# MCU.net
KiCad netlist of a schematic drawn in Altium Designer
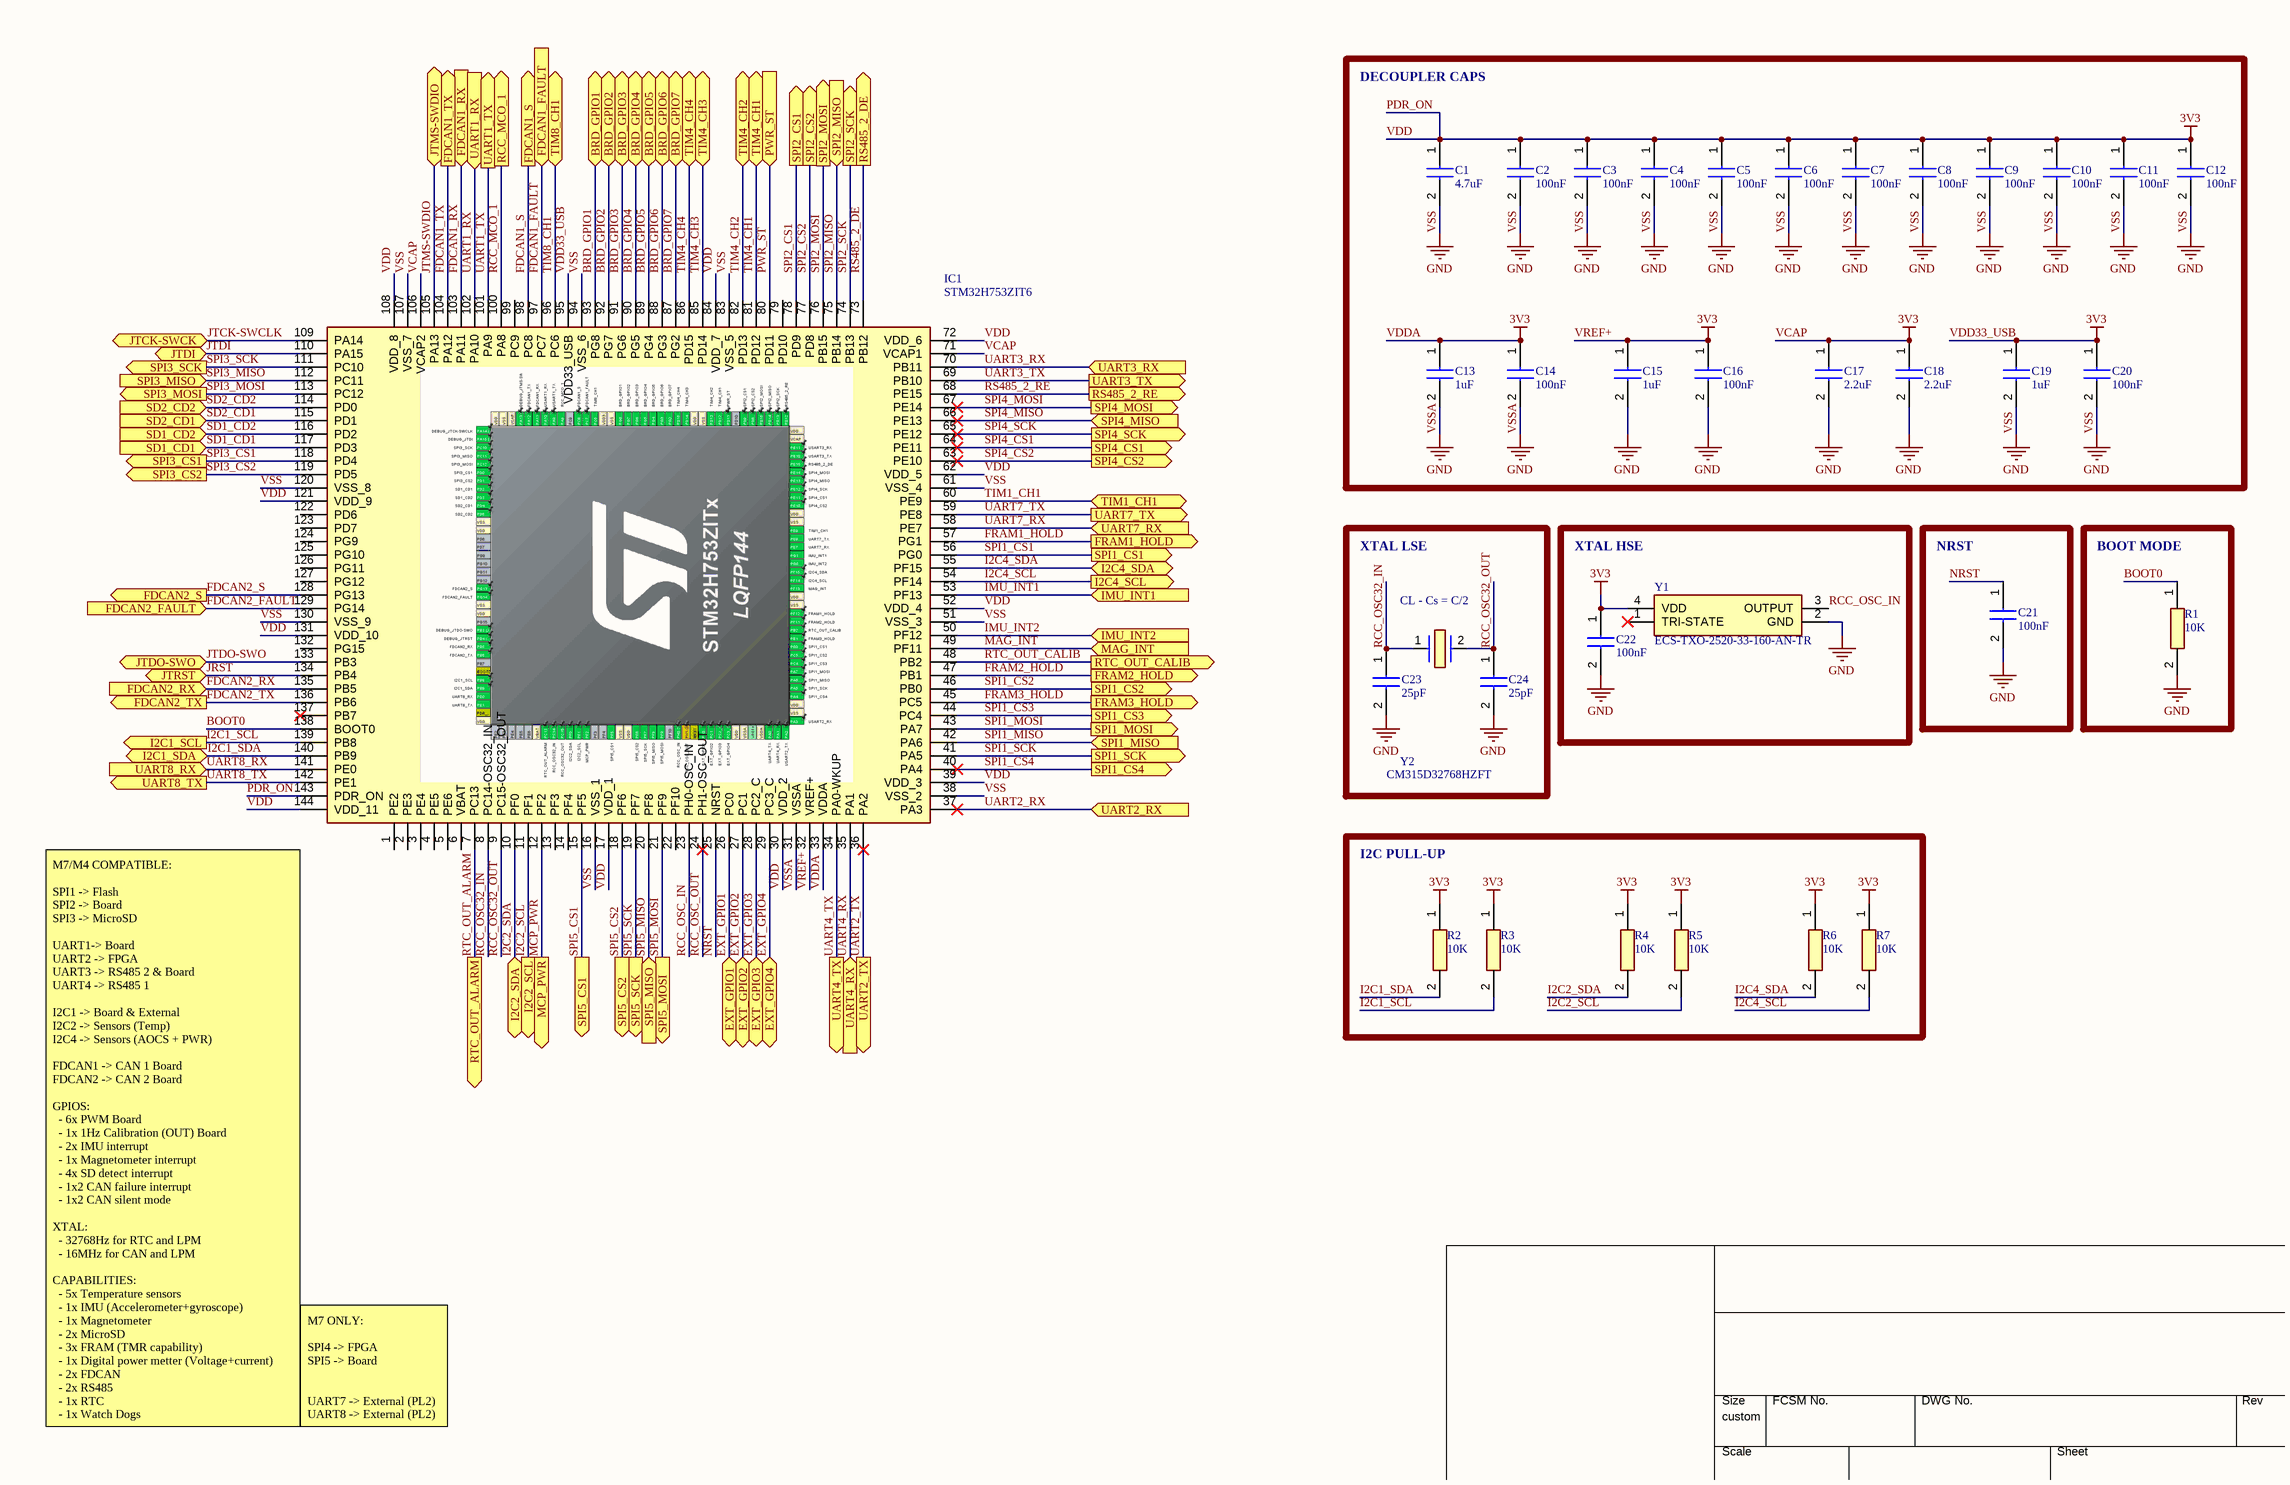
[diagram p0: MCU.SchDoc]

(export (version "E")
  (design (tool "Eeschema 10.0.6"))
  (components
    (comp (ref "C1")
      (value "4.7uF")
      (footprint "RT_IS:CAPC1608X90N")
      (description "4.7 µF ±10% 10V Ceramic Capacitor X5R 0603 (1608 Metric)")
      (fields
        (field (name "MANUFACTURER_PART_NUMBER") "CL10A475KP8NNNC")
        (field (name "MOUSER PART NUMBER") "187-CL10A475KP8NNNC")
      )
      (libsource (lib "*") (part "CL10A475KP8NNNC"))
    )
    (comp (ref "C2")
      (value "100nF")
      (footprint "RT_IS:CAPC1608X95N")
      (description "0.1 µF ±20% 16V Ceramic Capacitor X7R 0603 (1608 Metric)")
      (fields (field (name "MANUFACTURER_PART_NUMBER") "C0603C104M4RAC7867"))
      (libsource (lib "*") (part "C0603C104M4RAC7867"))
    )
    (comp (ref "C3")
      (value "100nF")
      (footprint "RT_IS:CAPC1608X95N")
      (description "0.1 µF ±20% 16V Ceramic Capacitor X7R 0603 (1608 Metric)")
      (fields (field (name "MANUFACTURER_PART_NUMBER") "C0603C104M4RAC7867"))
      (libsource (lib "*") (part "C0603C104M4RAC7867"))
    )
    (comp (ref "C4")
      (value "100nF")
      (footprint "RT_IS:CAPC1608X95N")
      (description "0.1 µF ±20% 16V Ceramic Capacitor X7R 0603 (1608 Metric)")
      (fields (field (name "MANUFACTURER_PART_NUMBER") "C0603C104M4RAC7867"))
      (libsource (lib "*") (part "C0603C104M4RAC7867"))
    )
    (comp (ref "C5")
      (value "100nF")
      (footprint "RT_IS:CAPC1608X95N")
      (description "0.1 µF ±20% 16V Ceramic Capacitor X7R 0603 (1608 Metric)")
      (fields (field (name "MANUFACTURER_PART_NUMBER") "C0603C104M4RAC7867"))
      (libsource (lib "*") (part "C0603C104M4RAC7867"))
    )
    (comp (ref "C6")
      (value "100nF")
      (footprint "RT_IS:CAPC1608X95N")
      (description "0.1 µF ±20% 16V Ceramic Capacitor X7R 0603 (1608 Metric)")
      (fields (field (name "MANUFACTURER_PART_NUMBER") "C0603C104M4RAC7867"))
      (libsource (lib "*") (part "C0603C104M4RAC7867"))
    )
    (comp (ref "C7")
      (value "100nF")
      (footprint "RT_IS:CAPC1608X95N")
      (description "0.1 µF ±20% 16V Ceramic Capacitor X7R 0603 (1608 Metric)")
      (fields (field (name "MANUFACTURER_PART_NUMBER") "C0603C104M4RAC7867"))
      (libsource (lib "*") (part "C0603C104M4RAC7867"))
    )
    (comp (ref "C8")
      (value "100nF")
      (footprint "RT_IS:CAPC1608X95N")
      (description "0.1 µF ±20% 16V Ceramic Capacitor X7R 0603 (1608 Metric)")
      (fields (field (name "MANUFACTURER_PART_NUMBER") "C0603C104M4RAC7867"))
      (libsource (lib "*") (part "C0603C104M4RAC7867"))
    )
    (comp (ref "C9")
      (value "100nF")
      (footprint "RT_IS:CAPC1608X95N")
      (description "0.1 µF ±20% 16V Ceramic Capacitor X7R 0603 (1608 Metric)")
      (fields (field (name "MANUFACTURER_PART_NUMBER") "C0603C104M4RAC7867"))
      (libsource (lib "*") (part "C0603C104M4RAC7867"))
    )
    (comp (ref "C10")
      (value "100nF")
      (footprint "RT_IS:CAPC1608X95N")
      (description "0.1 µF ±20% 16V Ceramic Capacitor X7R 0603 (1608 Metric)")
      (fields (field (name "MANUFACTURER_PART_NUMBER") "C0603C104M4RAC7867"))
      (libsource (lib "*") (part "C0603C104M4RAC7867"))
    )
    (comp (ref "C11")
      (value "100nF")
      (footprint "RT_IS:CAPC1608X95N")
      (description "0.1 µF ±20% 16V Ceramic Capacitor X7R 0603 (1608 Metric)")
      (fields (field (name "MANUFACTURER_PART_NUMBER") "C0603C104M4RAC7867"))
      (libsource (lib "*") (part "C0603C104M4RAC7867"))
    )
    (comp (ref "C12")
      (value "100nF")
      (footprint "RT_IS:CAPC1608X95N")
      (description "0.1 µF ±20% 16V Ceramic Capacitor X7R 0603 (1608 Metric)")
      (fields (field (name "MANUFACTURER_PART_NUMBER") "C0603C104M4RAC7867"))
      (libsource (lib "*") (part "C0603C104M4RAC7867"))
    )
    (comp (ref "C13")
      (value "1uF")
      (footprint "RT_IS:CAPC1608X90N")
      (description "1 µF ±10% 25V Ceramic Capacitor X5R 0603 (1608 Metric)")
      (fields
        (field (name "MANUFACTURER_PART_NUMBER") "CL10A105KA8NNNC")
        (field (name "MOUSER PART NUMBER") "187-CL10A105KA8NNNC")
      )
      (libsource (lib "*") (part "CL10A105KA8NNNC"))
    )
    (comp (ref "C14")
      (value "100nF")
      (footprint "RT_IS:CAPC1608X95N")
      (description "0.1 µF ±20% 16V Ceramic Capacitor X7R 0603 (1608 Metric)")
      (fields (field (name "MANUFACTURER_PART_NUMBER") "C0603C104M4RAC7867"))
      (libsource (lib "*") (part "C0603C104M4RAC7867"))
    )
    (comp (ref "C15")
      (value "1uF")
      (footprint "RT_IS:CAPC1608X90N")
      (description "1 µF ±10% 25V Ceramic Capacitor X5R 0603 (1608 Metric)")
      (fields
        (field (name "MANUFACTURER_PART_NUMBER") "CL10A105KA8NNNC")
        (field (name "MOUSER PART NUMBER") "187-CL10A105KA8NNNC")
      )
      (libsource (lib "*") (part "CL10A105KA8NNNC"))
    )
    (comp (ref "C16")
      (value "100nF")
      (footprint "RT_IS:CAPC1608X95N")
      (description "0.1 µF ±20% 16V Ceramic Capacitor X7R 0603 (1608 Metric)")
      (fields (field (name "MANUFACTURER_PART_NUMBER") "C0603C104M4RAC7867"))
      (libsource (lib "*") (part "C0603C104M4RAC7867"))
    )
    (comp (ref "C17")
      (value "2.2uF")
      (footprint "RT_IS:CAPC1608X90N")
      (description "2.2 µF ±10% 16V Ceramic Capacitor X5R 0603 (1608 Metric)")
      (fields
        (field (name "MANUFACTURER_PART_NUMBER") "CL10A225KO8NNNC")
        (field (name "MOUSER PART NUMBER") "187-CL10A225KO8NNNC")
      )
      (libsource (lib "*") (part "CL10A225KO8NNNC"))
    )
    (comp (ref "C18")
      (value "2.2uF")
      (footprint "RT_IS:CAPC1608X90N")
      (description "2.2 µF ±10% 16V Ceramic Capacitor X5R 0603 (1608 Metric)")
      (fields
        (field (name "MANUFACTURER_PART_NUMBER") "CL10A225KO8NNNC")
        (field (name "MOUSER PART NUMBER") "187-CL10A225KO8NNNC")
      )
      (libsource (lib "*") (part "CL10A225KO8NNNC"))
    )
    (comp (ref "C19")
      (value "1uF")
      (footprint "RT_IS:CAPC1608X90N")
      (description "1 µF ±10% 25V Ceramic Capacitor X5R 0603 (1608 Metric)")
      (fields
        (field (name "MANUFACTURER_PART_NUMBER") "CL10A105KA8NNNC")
        (field (name "MOUSER PART NUMBER") "187-CL10A105KA8NNNC")
      )
      (libsource (lib "*") (part "CL10A105KA8NNNC"))
    )
    (comp (ref "C20")
      (value "100nF")
      (footprint "RT_IS:CAPC1608X95N")
      (description "0.1 µF ±20% 16V Ceramic Capacitor X7R 0603 (1608 Metric)")
      (fields (field (name "MANUFACTURER_PART_NUMBER") "C0603C104M4RAC7867"))
      (libsource (lib "*") (part "C0603C104M4RAC7867"))
    )
    (comp (ref "C21")
      (value "100nF")
      (footprint "RT_IS:CAPC1608X95N")
      (description "0.1 µF ±20% 16V Ceramic Capacitor X7R 0603 (1608 Metric)")
      (fields (field (name "MANUFACTURER_PART_NUMBER") "C0603C104M4RAC7867"))
      (libsource (lib "*") (part "C0603C104M4RAC7867"))
    )
    (comp (ref "C22")
      (value "100nF")
      (footprint "RT_IS:CAPC1608X95N")
      (description "0.1 µF ±20% 16V Ceramic Capacitor X7R 0603 (1608 Metric)")
      (fields (field (name "MANUFACTURER_PART_NUMBER") "C0603C104M4RAC7867"))
      (libsource (lib "*") (part "C0603C104M4RAC7867"))
    )
    (comp (ref "C23")
      (value "25pF")
      (footprint "RT_IS:CAPC1608X90N")
      (description "22 pF ±1% 100V Ceramic Capacitor C0G, NP0 0603 (1608 Metric)")
      (fields (field (name "MANUFACTURER_PART_NUMBER") "GCM1885C2A220FA16D"))
      (libsource (lib "*") (part "GCM1885C2A220FA16D"))
    )
    (comp (ref "C24")
      (value "25pF")
      (footprint "RT_IS:CAPC1608X90N")
      (description "22 pF ±1% 100V Ceramic Capacitor C0G, NP0 0603 (1608 Metric)")
      (fields (field (name "MANUFACTURER_PART_NUMBER") "GCM1885C2A220FA16D"))
      (libsource (lib "*") (part "GCM1885C2A220FA16D"))
    )
    (comp (ref "IC1")
      (value "STM32H753ZIT6")
      (footprint "RT_IS:QFP50P2200X2200X160-144N")
      (fields (field (name "MOUSER PART NUMBER") "511-STM32H753ZIT6"))
      (libsource (lib "*") (part "STM32H753ZIT6"))
    )
    (comp (ref "R1")
      (value "10K")
      (footprint "RT_IS:RESC1508X50N")
      (description "10 kOhms ±1% 0.125W, 1/8W Chip Resistor 0603 (1608 Metric) Anti-Sulfur Thin Film")
      (fields
        (field (name "MANUFACTURER_PART_NUMBER") "RNCP0603FTD10K0")
        (field (name "MOUSER PART NUMBER") "708-RNCP0603FTD10K0")
      )
      (libsource (lib "*") (part "RNCP0603FTD10K0"))
    )
    (comp (ref "R2")
      (value "10K")
      (footprint "RT_IS:RESC1508X50N")
      (description "10 kOhms ±1% 0.125W, 1/8W Chip Resistor 0603 (1608 Metric) Anti-Sulfur Thin Film")
      (fields
        (field (name "MANUFACTURER_PART_NUMBER") "RNCP0603FTD10K0")
        (field (name "MOUSER PART NUMBER") "708-RNCP0603FTD10K0")
      )
      (libsource (lib "*") (part "RNCP0603FTD10K0"))
    )
    (comp (ref "R3")
      (value "10K")
      (footprint "RT_IS:RESC1508X50N")
      (description "10 kOhms ±1% 0.125W, 1/8W Chip Resistor 0603 (1608 Metric) Anti-Sulfur Thin Film")
      (fields
        (field (name "MANUFACTURER_PART_NUMBER") "RNCP0603FTD10K0")
        (field (name "MOUSER PART NUMBER") "708-RNCP0603FTD10K0")
      )
      (libsource (lib "*") (part "RNCP0603FTD10K0"))
    )
    (comp (ref "R4")
      (value "10K")
      (footprint "RT_IS:RESC1508X50N")
      (description "10 kOhms ±1% 0.125W, 1/8W Chip Resistor 0603 (1608 Metric) Anti-Sulfur Thin Film")
      (fields
        (field (name "MANUFACTURER_PART_NUMBER") "RNCP0603FTD10K0")
        (field (name "MOUSER PART NUMBER") "708-RNCP0603FTD10K0")
      )
      (libsource (lib "*") (part "RNCP0603FTD10K0"))
    )
    (comp (ref "R5")
      (value "10K")
      (footprint "RT_IS:RESC1508X50N")
      (description "10 kOhms ±1% 0.125W, 1/8W Chip Resistor 0603 (1608 Metric) Anti-Sulfur Thin Film")
      (fields
        (field (name "MANUFACTURER_PART_NUMBER") "RNCP0603FTD10K0")
        (field (name "MOUSER PART NUMBER") "708-RNCP0603FTD10K0")
      )
      (libsource (lib "*") (part "RNCP0603FTD10K0"))
    )
    (comp (ref "R6")
      (value "10K")
      (footprint "RT_IS:RESC1508X50N")
      (description "10 kOhms ±1% 0.125W, 1/8W Chip Resistor 0603 (1608 Metric) Anti-Sulfur Thin Film")
      (fields
        (field (name "MANUFACTURER_PART_NUMBER") "RNCP0603FTD10K0")
        (field (name "MOUSER PART NUMBER") "708-RNCP0603FTD10K0")
      )
      (libsource (lib "*") (part "RNCP0603FTD10K0"))
    )
    (comp (ref "R7")
      (value "10K")
      (footprint "RT_IS:RESC1508X50N")
      (description "10 kOhms ±1% 0.125W, 1/8W Chip Resistor 0603 (1608 Metric) Anti-Sulfur Thin Film")
      (fields
        (field (name "MANUFACTURER_PART_NUMBER") "RNCP0603FTD10K0")
        (field (name "MOUSER PART NUMBER") "708-RNCP0603FTD10K0")
      )
      (libsource (lib "*") (part "RNCP0603FTD10K0"))
    )
    (comp (ref "Y1")
      (value "ECS-TXO-2520-33-160-AN-TR")
      (footprint "RT_IS:ECSTXO252033160ANTR")
      (description "16 MHz TCXO HCMOS Oscillator 3.3V Enable/Disable 4-SMD, No Lead")
      (fields (field (name "MOUSER PART NUMBER") "520-T2520-33-160-ANT"))
      (libsource (lib "*") (part "ECS-TXO-2520-33-160-AN-TR"))
    )
    (comp (ref "Y2")
      (value "CM315D32768HZFT")
      (footprint "RT_IS:CM315D32768HZFT")
      (description "32.768 kHz ±5ppm Crystal 12.5pF 70 kOhms 2-SMD, No Lead")
      (libsource (lib "*") (part "CM315D32768HZFT"))
    )
  )
  (nets
    (net (code "1") (name "/BOOT0") (class "Default")
      (node (ref "IC1") (pin "138") (pinfunction "BOOT0_138") (pintype "passive"))
      (node (ref "R1") (pin "1") (pinfunction "1_1") (pintype "passive"))
    )
    (net (code "2") (name "/BRD_GPIO1") (class "Default")
      (node (ref "IC1") (pin "93") (pinfunction "PG8_93") (pintype "passive"))
    )
    (net (code "3") (name "/BRD_GPIO2") (class "Default")
      (node (ref "IC1") (pin "92") (pinfunction "PG7_92") (pintype "passive"))
    )
    (net (code "4") (name "/BRD_GPIO3") (class "Default")
      (node (ref "IC1") (pin "91") (pinfunction "PG6_91") (pintype "passive"))
    )
    (net (code "5") (name "/BRD_GPIO4") (class "Default")
      (node (ref "IC1") (pin "90") (pinfunction "PG5_90") (pintype "passive"))
    )
    (net (code "6") (name "/BRD_GPIO5") (class "Default")
      (node (ref "IC1") (pin "89") (pinfunction "PG4_89") (pintype "passive"))
    )
    (net (code "7") (name "/BRD_GPIO6") (class "Default")
      (node (ref "IC1") (pin "88") (pinfunction "PG3_88") (pintype "passive"))
    )
    (net (code "8") (name "/BRD_GPIO7") (class "Default")
      (node (ref "IC1") (pin "87") (pinfunction "PG2_87") (pintype "passive"))
    )
    (net (code "9") (name "/EXT_GPIO1") (class "Default")
      (node (ref "IC1") (pin "26") (pinfunction "PC0_26") (pintype "passive"))
    )
    (net (code "10") (name "/EXT_GPIO2") (class "Default")
      (node (ref "IC1") (pin "27") (pinfunction "PC1_27") (pintype "passive"))
    )
    (net (code "11") (name "/EXT_GPIO3") (class "Default")
      (node (ref "IC1") (pin "28") (pinfunction "PC2_C_28") (pintype "passive"))
    )
    (net (code "12") (name "/EXT_GPIO4") (class "Default")
      (node (ref "IC1") (pin "29") (pinfunction "PC3_C_29") (pintype "passive"))
    )
    (net (code "13") (name "/FDCAN1_FAULT") (class "Default")
      (node (ref "IC1") (pin "97") (pinfunction "PC7_97") (pintype "passive"))
    )
    (net (code "14") (name "/FDCAN1_RX") (class "Default")
      (node (ref "IC1") (pin "103") (pinfunction "PA11_103") (pintype "passive"))
    )
    (net (code "15") (name "/FDCAN1_S") (class "Default")
      (node (ref "IC1") (pin "98") (pinfunction "PC8_98") (pintype "passive"))
    )
    (net (code "16") (name "/FDCAN1_TX") (class "Default")
      (node (ref "IC1") (pin "104") (pinfunction "PA12_104") (pintype "passive"))
    )
    (net (code "17") (name "/FDCAN2_FAULT") (class "Default")
      (node (ref "IC1") (pin "129") (pinfunction "PG14_129") (pintype "passive"))
    )
    (net (code "18") (name "/FDCAN2_RX") (class "Default")
      (node (ref "IC1") (pin "135") (pinfunction "PB5_135") (pintype "passive"))
    )
    (net (code "19") (name "/FDCAN2_S") (class "Default")
      (node (ref "IC1") (pin "128") (pinfunction "PG13_128") (pintype "passive"))
    )
    (net (code "20") (name "/FDCAN2_TX") (class "Default")
      (node (ref "IC1") (pin "136") (pinfunction "PB6_136") (pintype "passive"))
    )
    (net (code "21") (name "/FRAM1_HOLD") (class "Default")
      (node (ref "IC1") (pin "57") (pinfunction "PG1_57") (pintype "passive"))
    )
    (net (code "22") (name "/FRAM2_HOLD") (class "Default")
      (node (ref "IC1") (pin "47") (pinfunction "PB1_47") (pintype "passive"))
    )
    (net (code "23") (name "/FRAM3_HOLD") (class "Default")
      (node (ref "IC1") (pin "45") (pinfunction "PC5_45") (pintype "passive"))
    )
    (net (code "24") (name "/I2C1_SCL") (class "Default")
      (node (ref "IC1") (pin "139") (pinfunction "PB8_139") (pintype "passive"))
      (node (ref "R3") (pin "2") (pinfunction "2_2") (pintype "passive"))
    )
    (net (code "25") (name "/I2C1_SDA") (class "Default")
      (node (ref "IC1") (pin "140") (pinfunction "PB9_140") (pintype "passive"))
      (node (ref "R2") (pin "2") (pinfunction "2_2") (pintype "passive"))
    )
    (net (code "26") (name "/I2C2_SCL") (class "Default")
      (node (ref "IC1") (pin "11") (pinfunction "PF1_11") (pintype "passive"))
      (node (ref "R5") (pin "2") (pinfunction "2_2") (pintype "passive"))
    )
    (net (code "27") (name "/I2C2_SDA") (class "Default")
      (node (ref "IC1") (pin "10") (pinfunction "PF0_10") (pintype "passive"))
      (node (ref "R4") (pin "2") (pinfunction "2_2") (pintype "passive"))
    )
    (net (code "28") (name "/I2C4_SCL") (class "Default")
      (node (ref "IC1") (pin "54") (pinfunction "PF14_54") (pintype "passive"))
      (node (ref "R7") (pin "2") (pinfunction "2_2") (pintype "passive"))
    )
    (net (code "29") (name "/I2C4_SDA") (class "Default")
      (node (ref "IC1") (pin "55") (pinfunction "PF15_55") (pintype "passive"))
      (node (ref "R6") (pin "2") (pinfunction "2_2") (pintype "passive"))
    )
    (net (code "30") (name "/IMU_INT1") (class "Default")
      (node (ref "IC1") (pin "53") (pinfunction "PF13_53") (pintype "passive"))
    )
    (net (code "31") (name "/IMU_INT2") (class "Default")
      (node (ref "IC1") (pin "50") (pinfunction "PF12_50") (pintype "passive"))
    )
    (net (code "32") (name "/JRST") (class "Default")
      (node (ref "IC1") (pin "134") (pinfunction "PB4_134") (pintype "passive"))
    )
    (net (code "33") (name "/JTCK-SWCLK") (class "Default")
      (node (ref "IC1") (pin "109") (pinfunction "PA14_109") (pintype "passive"))
    )
    (net (code "34") (name "/JTDI") (class "Default")
      (node (ref "IC1") (pin "110") (pinfunction "PA15_110") (pintype "passive"))
    )
    (net (code "35") (name "/JTDO-SWO") (class "Default")
      (node (ref "IC1") (pin "133") (pinfunction "PB3_133") (pintype "passive"))
    )
    (net (code "36") (name "/JTMS-SWDIO") (class "Default")
      (node (ref "IC1") (pin "105") (pinfunction "PA13_105") (pintype "passive"))
    )
    (net (code "37") (name "/MAG_INT") (class "Default")
      (node (ref "IC1") (pin "49") (pinfunction "PF11_49") (pintype "passive"))
    )
    (net (code "38") (name "/MCP_PWR") (class "Default")
      (node (ref "IC1") (pin "12") (pinfunction "PF2_12") (pintype "passive"))
    )
    (net (code "39") (name "/NRST") (class "Default")
      (node (ref "C21") (pin "1") (pinfunction "1_1") (pintype "passive"))
      (node (ref "IC1") (pin "25") (pinfunction "NRST_25") (pintype "passive"))
    )
    (net (code "40") (name "/PWR_ST") (class "Default")
      (node (ref "IC1") (pin "80") (pinfunction "PD11_80") (pintype "passive"))
    )
    (net (code "41") (name "/RCC_MCO_1") (class "Default")
      (node (ref "IC1") (pin "100") (pinfunction "PA8_100") (pintype "passive"))
    )
    (net (code "42") (name "/RCC_OSC32_IN") (class "Default")
      (node (ref "C23") (pin "1") (pinfunction "1_1") (pintype "passive"))
      (node (ref "IC1") (pin "8") (pinfunction "PC14-OSC32_IN_8") (pintype "passive"))
      (node (ref "Y2") (pin "1") (pinfunction "1_1") (pintype "passive"))
    )
    (net (code "43") (name "/RCC_OSC32_OUT") (class "Default")
      (node (ref "C24") (pin "1") (pinfunction "1_1") (pintype "passive"))
      (node (ref "IC1") (pin "9") (pinfunction "PC15-OSC32_OUT_9") (pintype "passive"))
      (node (ref "Y2") (pin "2") (pinfunction "2_2") (pintype "passive"))
    )
    (net (code "44") (name "/RCC_OSC_IN") (class "Default")
      (node (ref "IC1") (pin "23") (pinfunction "PH0-OSC_IN_23") (pintype "passive"))
      (node (ref "Y1") (pin "3") (pinfunction "OUTPUT_3") (pintype "passive"))
    )
    (net (code "45") (name "/RCC_OSC_OUT") (class "Default")
      (node (ref "IC1") (pin "24") (pinfunction "PH1-OSC_OUT_24") (pintype "passive+no_connect"))
    )
    (net (code "46") (name "/RS485_2_DE") (class "Default")
      (node (ref "IC1") (pin "73") (pinfunction "PB12_73") (pintype "passive"))
    )
    (net (code "47") (name "/RS485_2_RE") (class "Default")
      (node (ref "IC1") (pin "68") (pinfunction "PE15_68") (pintype "passive"))
    )
    (net (code "48") (name "/RTC_OUT_ALARM") (class "Default")
      (node (ref "IC1") (pin "7") (pinfunction "PC13_7") (pintype "passive"))
    )
    (net (code "49") (name "/RTC_OUT_CALIB") (class "Default")
      (node (ref "IC1") (pin "48") (pinfunction "PB2_48") (pintype "passive"))
    )
    (net (code "50") (name "/SD1_CD1") (class "Default")
      (node (ref "IC1") (pin "117") (pinfunction "PD3_117") (pintype "passive"))
    )
    (net (code "51") (name "/SD1_CD2") (class "Default")
      (node (ref "IC1") (pin "116") (pinfunction "PD2_116") (pintype "passive"))
    )
    (net (code "52") (name "/SD2_CD1") (class "Default")
      (node (ref "IC1") (pin "115") (pinfunction "PD1_115") (pintype "passive"))
    )
    (net (code "53") (name "/SD2_CD2") (class "Default")
      (node (ref "IC1") (pin "114") (pinfunction "PD0_114") (pintype "passive"))
    )
    (net (code "54") (name "/SPI1_CS1") (class "Default")
      (node (ref "IC1") (pin "56") (pinfunction "PG0_56") (pintype "passive"))
    )
    (net (code "55") (name "/SPI1_CS2") (class "Default")
      (node (ref "IC1") (pin "46") (pinfunction "PB0_46") (pintype "passive"))
    )
    (net (code "56") (name "/SPI1_CS3") (class "Default")
      (node (ref "IC1") (pin "44") (pinfunction "PC4_44") (pintype "passive"))
    )
    (net (code "57") (name "/SPI1_CS4") (class "Default")
      (node (ref "IC1") (pin "40") (pinfunction "PA4_40") (pintype "passive+no_connect"))
    )
    (net (code "58") (name "/SPI1_MISO") (class "Default")
      (node (ref "IC1") (pin "42") (pinfunction "PA6_42") (pintype "passive"))
    )
    (net (code "59") (name "/SPI1_MOSI") (class "Default")
      (node (ref "IC1") (pin "43") (pinfunction "PA7_43") (pintype "passive"))
    )
    (net (code "60") (name "/SPI1_SCK") (class "Default")
      (node (ref "IC1") (pin "41") (pinfunction "PA5_41") (pintype "passive"))
    )
    (net (code "61") (name "/SPI2_CS1") (class "Default")
      (node (ref "IC1") (pin "78") (pinfunction "PD9_78") (pintype "passive"))
    )
    (net (code "62") (name "/SPI2_CS2") (class "Default")
      (node (ref "IC1") (pin "77") (pinfunction "PD8_77") (pintype "passive"))
    )
    (net (code "63") (name "/SPI2_MISO") (class "Default")
      (node (ref "IC1") (pin "75") (pinfunction "PB14_75") (pintype "passive"))
    )
    (net (code "64") (name "/SPI2_MOSI") (class "Default")
      (node (ref "IC1") (pin "76") (pinfunction "PB15_76") (pintype "passive"))
    )
    (net (code "65") (name "/SPI2_SCK") (class "Default")
      (node (ref "IC1") (pin "74") (pinfunction "PB13_74") (pintype "passive"))
    )
    (net (code "66") (name "/SPI3_CS1") (class "Default")
      (node (ref "IC1") (pin "118") (pinfunction "PD4_118") (pintype "passive"))
    )
    (net (code "67") (name "/SPI3_CS2") (class "Default")
      (node (ref "IC1") (pin "119") (pinfunction "PD5_119") (pintype "passive"))
    )
    (net (code "68") (name "/SPI3_MISO") (class "Default")
      (node (ref "IC1") (pin "112") (pinfunction "PC11_112") (pintype "passive"))
    )
    (net (code "69") (name "/SPI3_MOSI") (class "Default")
      (node (ref "IC1") (pin "113") (pinfunction "PC12_113") (pintype "passive"))
    )
    (net (code "70") (name "/SPI3_SCK") (class "Default")
      (node (ref "IC1") (pin "111") (pinfunction "PC10_111") (pintype "passive"))
    )
    (net (code "71") (name "/SPI4_CS1") (class "Default")
      (node (ref "IC1") (pin "64") (pinfunction "PE11_64") (pintype "passive+no_connect"))
    )
    (net (code "72") (name "/SPI4_CS2") (class "Default")
      (node (ref "IC1") (pin "63") (pinfunction "PE10_63") (pintype "passive+no_connect"))
    )
    (net (code "73") (name "/SPI4_MISO") (class "Default")
      (node (ref "IC1") (pin "66") (pinfunction "PE13_66") (pintype "passive+no_connect"))
    )
    (net (code "74") (name "/SPI4_MOSI") (class "Default")
      (node (ref "IC1") (pin "67") (pinfunction "PE14_67") (pintype "passive+no_connect"))
    )
    (net (code "75") (name "/SPI4_SCK") (class "Default")
      (node (ref "IC1") (pin "65") (pinfunction "PE12_65") (pintype "passive+no_connect"))
    )
    (net (code "76") (name "/SPI5_CS1") (class "Default")
      (node (ref "IC1") (pin "15") (pinfunction "PF5_15") (pintype "passive"))
    )
    (net (code "77") (name "/SPI5_CS2") (class "Default")
      (node (ref "IC1") (pin "18") (pinfunction "PF6_18") (pintype "passive"))
    )
    (net (code "78") (name "/SPI5_MISO") (class "Default")
      (node (ref "IC1") (pin "20") (pinfunction "PF8_20") (pintype "passive"))
    )
    (net (code "79") (name "/SPI5_MOSI") (class "Default")
      (node (ref "IC1") (pin "21") (pinfunction "PF9_21") (pintype "passive"))
    )
    (net (code "80") (name "/SPI5_SCK") (class "Default")
      (node (ref "IC1") (pin "19") (pinfunction "PF7_19") (pintype "passive"))
    )
    (net (code "81") (name "/TIM1_CH1") (class "Default")
      (node (ref "IC1") (pin "60") (pinfunction "PE9_60") (pintype "passive"))
    )
    (net (code "82") (name "/TIM4_CH1") (class "Default")
      (node (ref "IC1") (pin "81") (pinfunction "PD12_81") (pintype "passive"))
    )
    (net (code "83") (name "/TIM4_CH2") (class "Default")
      (node (ref "IC1") (pin "82") (pinfunction "PD13_82") (pintype "passive"))
    )
    (net (code "84") (name "/TIM4_CH3") (class "Default")
      (node (ref "IC1") (pin "85") (pinfunction "PD14_85") (pintype "passive"))
    )
    (net (code "85") (name "/TIM4_CH4") (class "Default")
      (node (ref "IC1") (pin "86") (pinfunction "PD15_86") (pintype "passive"))
    )
    (net (code "86") (name "/TIM8_CH1") (class "Default")
      (node (ref "IC1") (pin "96") (pinfunction "PC6_96") (pintype "passive"))
    )
    (net (code "87") (name "/UART1_RX") (class "Default")
      (node (ref "IC1") (pin "102") (pinfunction "PA10_102") (pintype "passive"))
    )
    (net (code "88") (name "/UART1_TX") (class "Default")
      (node (ref "IC1") (pin "101") (pinfunction "PA9_101") (pintype "passive"))
    )
    (net (code "89") (name "/UART2_RX") (class "Default")
      (node (ref "IC1") (pin "37") (pinfunction "PA3_37") (pintype "passive+no_connect"))
    )
    (net (code "90") (name "/UART2_TX") (class "Default")
      (node (ref "IC1") (pin "36") (pinfunction "PA2_36") (pintype "passive+no_connect"))
    )
    (net (code "91") (name "/UART3_RX") (class "Default")
      (node (ref "IC1") (pin "70") (pinfunction "PB11_70") (pintype "passive"))
    )
    (net (code "92") (name "/UART3_TX") (class "Default")
      (node (ref "IC1") (pin "69") (pinfunction "PB10_69") (pintype "passive"))
    )
    (net (code "93") (name "/UART4_RX") (class "Default")
      (node (ref "IC1") (pin "35") (pinfunction "PA1_35") (pintype "passive"))
    )
    (net (code "94") (name "/UART4_TX") (class "Default")
      (node (ref "IC1") (pin "34") (pinfunction "PA0-WKUP_34") (pintype "passive"))
    )
    (net (code "95") (name "/UART7_RX") (class "Default")
      (node (ref "IC1") (pin "58") (pinfunction "PE7_58") (pintype "passive"))
    )
    (net (code "96") (name "/UART7_TX") (class "Default")
      (node (ref "IC1") (pin "59") (pinfunction "PE8_59") (pintype "passive"))
    )
    (net (code "97") (name "/UART8_RX") (class "Default")
      (node (ref "IC1") (pin "141") (pinfunction "PE0_141") (pintype "passive"))
    )
    (net (code "98") (name "/UART8_TX") (class "Default")
      (node (ref "IC1") (pin "142") (pinfunction "PE1_142") (pintype "passive"))
    )
    (net (code "99") (name "3V3") (class "Default")
      (node (ref "C1") (pin "1") (pinfunction "1_1") (pintype "passive"))
      (node (ref "C10") (pin "1") (pinfunction "1_1") (pintype "passive"))
      (node (ref "C11") (pin "1") (pinfunction "1_1") (pintype "passive"))
      (node (ref "C12") (pin "1") (pinfunction "1_1") (pintype "passive"))
      (node (ref "C13") (pin "1") (pinfunction "1_1") (pintype "passive"))
      (node (ref "C14") (pin "1") (pinfunction "1_1") (pintype "passive"))
      (node (ref "C15") (pin "1") (pinfunction "1_1") (pintype "passive"))
      (node (ref "C16") (pin "1") (pinfunction "1_1") (pintype "passive"))
      (node (ref "C17") (pin "1") (pinfunction "1_1") (pintype "passive"))
      (node (ref "C18") (pin "1") (pinfunction "1_1") (pintype "passive"))
      (node (ref "C19") (pin "1") (pinfunction "1_1") (pintype "passive"))
      (node (ref "C2") (pin "1") (pinfunction "1_1") (pintype "passive"))
      (node (ref "C20") (pin "1") (pinfunction "1_1") (pintype "passive"))
      (node (ref "C22") (pin "1") (pinfunction "1_1") (pintype "passive"))
      (node (ref "C3") (pin "1") (pinfunction "1_1") (pintype "passive"))
      (node (ref "C4") (pin "1") (pinfunction "1_1") (pintype "passive"))
      (node (ref "C5") (pin "1") (pinfunction "1_1") (pintype "passive"))
      (node (ref "C6") (pin "1") (pinfunction "1_1") (pintype "passive"))
      (node (ref "C7") (pin "1") (pinfunction "1_1") (pintype "passive"))
      (node (ref "C8") (pin "1") (pinfunction "1_1") (pintype "passive"))
      (node (ref "C9") (pin "1") (pinfunction "1_1") (pintype "passive"))
      (node (ref "IC1") (pin "106") (pinfunction "VCAP2_106") (pintype "power_in"))
      (node (ref "IC1") (pin "108") (pinfunction "VDD_8_108") (pintype "power_in"))
      (node (ref "IC1") (pin "121") (pinfunction "VDD_9_121") (pintype "power_in"))
      (node (ref "IC1") (pin "131") (pinfunction "VDD_10_131") (pintype "power_in"))
      (node (ref "IC1") (pin "143") (pinfunction "PDR_ON_143") (pintype "passive"))
      (node (ref "IC1") (pin "144") (pinfunction "VDD_11_144") (pintype "power_in"))
      (node (ref "IC1") (pin "17") (pinfunction "VDD_1_17") (pintype "power_in"))
      (node (ref "IC1") (pin "30") (pinfunction "VDD_2_30") (pintype "power_in"))
      (node (ref "IC1") (pin "32") (pinfunction "VREF+_32") (pintype "passive"))
      (node (ref "IC1") (pin "33") (pinfunction "VDDA_33") (pintype "power_in"))
      (node (ref "IC1") (pin "39") (pinfunction "VDD_3_39") (pintype "power_in"))
      (node (ref "IC1") (pin "52") (pinfunction "VDD_4_52") (pintype "power_in"))
      (node (ref "IC1") (pin "62") (pinfunction "VDD_5_62") (pintype "power_in"))
      (node (ref "IC1") (pin "71") (pinfunction "VCAP1_71") (pintype "power_in"))
      (node (ref "IC1") (pin "72") (pinfunction "VDD_6_72") (pintype "power_in"))
      (node (ref "IC1") (pin "84") (pinfunction "VDD_7_84") (pintype "power_in"))
      (node (ref "IC1") (pin "95") (pinfunction "VDD33_USB_95") (pintype "power_in"))
      (node (ref "R2") (pin "1") (pinfunction "1_1") (pintype "passive"))
      (node (ref "R3") (pin "1") (pinfunction "1_1") (pintype "passive"))
      (node (ref "R4") (pin "1") (pinfunction "1_1") (pintype "passive"))
      (node (ref "R5") (pin "1") (pinfunction "1_1") (pintype "passive"))
      (node (ref "R6") (pin "1") (pinfunction "1_1") (pintype "passive"))
      (node (ref "R7") (pin "1") (pinfunction "1_1") (pintype "passive"))
      (node (ref "Y1") (pin "4") (pinfunction "VDD_4") (pintype "passive"))
    )
    (net (code "100") (name "GND") (class "Default")
      (node (ref "C1") (pin "2") (pinfunction "2_2") (pintype "passive"))
      (node (ref "C10") (pin "2") (pinfunction "2_2") (pintype "passive"))
      (node (ref "C11") (pin "2") (pinfunction "2_2") (pintype "passive"))
      (node (ref "C12") (pin "2") (pinfunction "2_2") (pintype "passive"))
      (node (ref "C13") (pin "2") (pinfunction "2_2") (pintype "passive"))
      (node (ref "C14") (pin "2") (pinfunction "2_2") (pintype "passive"))
      (node (ref "C15") (pin "2") (pinfunction "2_2") (pintype "passive"))
      (node (ref "C16") (pin "2") (pinfunction "2_2") (pintype "passive"))
      (node (ref "C17") (pin "2") (pinfunction "2_2") (pintype "passive"))
      (node (ref "C18") (pin "2") (pinfunction "2_2") (pintype "passive"))
      (node (ref "C19") (pin "2") (pinfunction "2_2") (pintype "passive"))
      (node (ref "C2") (pin "2") (pinfunction "2_2") (pintype "passive"))
      (node (ref "C20") (pin "2") (pinfunction "2_2") (pintype "passive"))
      (node (ref "C21") (pin "2") (pinfunction "2_2") (pintype "passive"))
      (node (ref "C22") (pin "2") (pinfunction "2_2") (pintype "passive"))
      (node (ref "C23") (pin "2") (pinfunction "2_2") (pintype "passive"))
      (node (ref "C24") (pin "2") (pinfunction "2_2") (pintype "passive"))
      (node (ref "C3") (pin "2") (pinfunction "2_2") (pintype "passive"))
      (node (ref "C4") (pin "2") (pinfunction "2_2") (pintype "passive"))
      (node (ref "C5") (pin "2") (pinfunction "2_2") (pintype "passive"))
      (node (ref "C6") (pin "2") (pinfunction "2_2") (pintype "passive"))
      (node (ref "C7") (pin "2") (pinfunction "2_2") (pintype "passive"))
      (node (ref "C8") (pin "2") (pinfunction "2_2") (pintype "passive"))
      (node (ref "C9") (pin "2") (pinfunction "2_2") (pintype "passive"))
      (node (ref "IC1") (pin "107") (pinfunction "VSS_7_107") (pintype "power_in"))
      (node (ref "IC1") (pin "120") (pinfunction "VSS_8_120") (pintype "power_in"))
      (node (ref "IC1") (pin "130") (pinfunction "VSS_9_130") (pintype "power_in"))
      (node (ref "IC1") (pin "16") (pinfunction "VSS_1_16") (pintype "power_in"))
      (node (ref "IC1") (pin "31") (pinfunction "VSSA_31") (pintype "power_in"))
      (node (ref "IC1") (pin "38") (pinfunction "VSS_2_38") (pintype "power_in"))
      (node (ref "IC1") (pin "51") (pinfunction "VSS_3_51") (pintype "power_in"))
      (node (ref "IC1") (pin "61") (pinfunction "VSS_4_61") (pintype "power_in"))
      (node (ref "IC1") (pin "83") (pinfunction "VSS_5_83") (pintype "power_in"))
      (node (ref "IC1") (pin "94") (pinfunction "VSS_6_94") (pintype "power_in"))
      (node (ref "R1") (pin "2") (pinfunction "2_2") (pintype "passive"))
      (node (ref "Y1") (pin "2") (pinfunction "GND_2") (pintype "passive"))
    )
    (net (code "101") (name "unconnected-(IC1-PB7-Pad137)") (class "Default")
      (node (ref "IC1") (pin "137") (pinfunction "PB7_137") (pintype "passive+no_connect"))
    )
    (net (code "102") (name "unconnected-(IC1-PC9-Pad99)") (class "Default")
      (node (ref "IC1") (pin "99") (pinfunction "PC9_99") (pintype "passive"))
    )
    (net (code "103") (name "unconnected-(IC1-PD6-Pad122)") (class "Default")
      (node (ref "IC1") (pin "122") (pinfunction "PD6_122") (pintype "passive"))
    )
    (net (code "104") (name "unconnected-(IC1-PD7-Pad123)") (class "Default")
      (node (ref "IC1") (pin "123") (pinfunction "PD7_123") (pintype "passive"))
    )
    (net (code "105") (name "unconnected-(IC1-PD10-Pad79)") (class "Default")
      (node (ref "IC1") (pin "79") (pinfunction "PD10_79") (pintype "passive"))
    )
    (net (code "106") (name "unconnected-(IC1-PE2-Pad1)") (class "Default")
      (node (ref "IC1") (pin "1") (pinfunction "PE2_1") (pintype "passive"))
    )
    (net (code "107") (name "unconnected-(IC1-PE3-Pad2)") (class "Default")
      (node (ref "IC1") (pin "2") (pinfunction "PE3_2") (pintype "passive"))
    )
    (net (code "108") (name "unconnected-(IC1-PE4-Pad3)") (class "Default")
      (node (ref "IC1") (pin "3") (pinfunction "PE4_3") (pintype "passive"))
    )
    (net (code "109") (name "unconnected-(IC1-PE5-Pad4)") (class "Default")
      (node (ref "IC1") (pin "4") (pinfunction "PE5_4") (pintype "passive"))
    )
    (net (code "110") (name "unconnected-(IC1-PE6-Pad5)") (class "Default")
      (node (ref "IC1") (pin "5") (pinfunction "PE6_5") (pintype "passive"))
    )
    (net (code "111") (name "unconnected-(IC1-PF3-Pad13)") (class "Default")
      (node (ref "IC1") (pin "13") (pinfunction "PF3_13") (pintype "passive"))
    )
    (net (code "112") (name "unconnected-(IC1-PF4-Pad14)") (class "Default")
      (node (ref "IC1") (pin "14") (pinfunction "PF4_14") (pintype "passive"))
    )
    (net (code "113") (name "unconnected-(IC1-PF10-Pad22)") (class "Default")
      (node (ref "IC1") (pin "22") (pinfunction "PF10_22") (pintype "passive"))
    )
    (net (code "114") (name "unconnected-(IC1-PG9-Pad124)") (class "Default")
      (node (ref "IC1") (pin "124") (pinfunction "PG9_124") (pintype "passive"))
    )
    (net (code "115") (name "unconnected-(IC1-PG10-Pad125)") (class "Default")
      (node (ref "IC1") (pin "125") (pinfunction "PG10_125") (pintype "passive"))
    )
    (net (code "116") (name "unconnected-(IC1-PG11-Pad126)") (class "Default")
      (node (ref "IC1") (pin "126") (pinfunction "PG11_126") (pintype "passive"))
    )
    (net (code "117") (name "unconnected-(IC1-PG12-Pad127)") (class "Default")
      (node (ref "IC1") (pin "127") (pinfunction "PG12_127") (pintype "passive"))
    )
    (net (code "118") (name "unconnected-(IC1-PG15-Pad132)") (class "Default")
      (node (ref "IC1") (pin "132") (pinfunction "PG15_132") (pintype "passive"))
    )
    (net (code "119") (name "unconnected-(IC1-VBAT-Pad6)") (class "Default")
      (node (ref "IC1") (pin "6") (pinfunction "VBAT_6") (pintype "power_in"))
    )
    (net (code "120") (name "unconnected-(Y1-TRI-STATE-Pad1)") (class "Default")
      (node (ref "Y1") (pin "1") (pinfunction "TRI-STATE_1") (pintype "passive+no_connect"))
    )
  )
)
